# UV_LED.net
KiCad netlist of a schematic drawn in Altium Designer
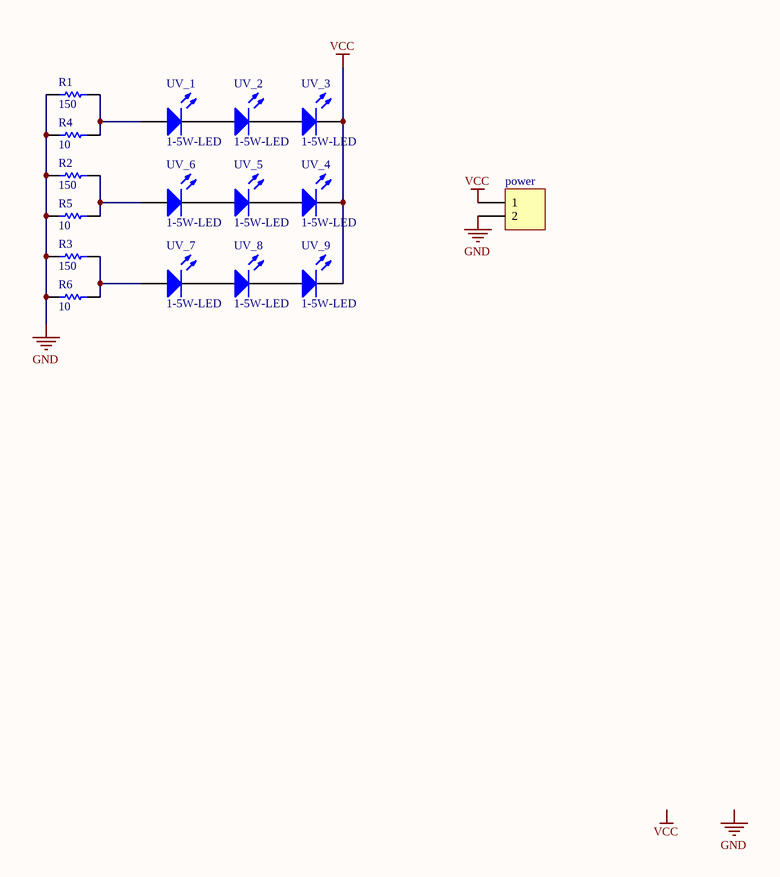
[diagram p0: UV LED.SchDoc]

(export (version "E")
  (design (tool "Eeschema 10.0.6"))
  (components
    (comp (ref "power")
      (value "Header 2")
      (footprint "HDR1X2")
      (description "Header, 2-Pin")
      (fields (field (name "PUBLISHER") "Altium Limited"))
      (libsource (lib "Miscellaneous Connectors") (part "Header 2"))
    )
    (comp (ref "R1")
      (value "150")
      (footprint "AXIAL-0.3")
      (description "Resistor")
      (fields (field (name "Comment") "Res1") (field (name "PUBLISHER") "Altium Limited"))
      (libsource (lib "Miscellaneous Devices") (part "Res1"))
    )
    (comp (ref "R2")
      (value "150")
      (footprint "AXIAL-0.3")
      (description "Resistor")
      (fields (field (name "Comment") "Res1") (field (name "PUBLISHER") "Altium Limited"))
      (libsource (lib "Miscellaneous Devices") (part "Res1"))
    )
    (comp (ref "R3")
      (value "150")
      (footprint "AXIAL-0.3")
      (description "Resistor")
      (fields (field (name "Comment") "Res1") (field (name "PUBLISHER") "Altium Limited"))
      (libsource (lib "Miscellaneous Devices") (part "Res1"))
    )
    (comp (ref "R4")
      (value "10")
      (footprint "AXIAL-0.3")
      (description "Resistor")
      (fields (field (name "Comment") "Res1") (field (name "PUBLISHER") "Altium Limited"))
      (libsource (lib "Miscellaneous Devices") (part "Res1"))
    )
    (comp (ref "R5")
      (value "10")
      (footprint "AXIAL-0.3")
      (description "Resistor")
      (fields (field (name "Comment") "Res1") (field (name "PUBLISHER") "Altium Limited"))
      (libsource (lib "Miscellaneous Devices") (part "Res1"))
    )
    (comp (ref "R6")
      (value "10")
      (footprint "AXIAL-0.3")
      (description "Resistor")
      (fields (field (name "Comment") "Res1") (field (name "PUBLISHER") "Altium Limited"))
      (libsource (lib "Miscellaneous Devices") (part "Res1"))
    )
    (comp (ref "UV_1")
      (value "1-5W-LED")
      (footprint "Highpwr_SMT_LED")
      (libsource (lib "arad") (part "1-5W-LED"))
    )
    (comp (ref "UV_2")
      (value "1-5W-LED")
      (footprint "Highpwr_SMT_LED")
      (libsource (lib "arad") (part "1-5W-LED"))
    )
    (comp (ref "UV_3")
      (value "1-5W-LED")
      (footprint "Highpwr_SMT_LED")
      (libsource (lib "arad") (part "1-5W-LED"))
    )
    (comp (ref "UV_4")
      (value "1-5W-LED")
      (footprint "Highpwr_SMT_LED")
      (libsource (lib "arad") (part "1-5W-LED"))
    )
    (comp (ref "UV_5")
      (value "1-5W-LED")
      (footprint "Highpwr_SMT_LED")
      (libsource (lib "arad") (part "1-5W-LED"))
    )
    (comp (ref "UV_6")
      (value "1-5W-LED")
      (footprint "Highpwr_SMT_LED")
      (libsource (lib "arad") (part "1-5W-LED"))
    )
    (comp (ref "UV_7")
      (value "1-5W-LED")
      (footprint "Highpwr_SMT_LED")
      (libsource (lib "arad") (part "1-5W-LED"))
    )
    (comp (ref "UV_8")
      (value "1-5W-LED")
      (footprint "Highpwr_SMT_LED")
      (libsource (lib "arad") (part "1-5W-LED"))
    )
    (comp (ref "UV_9")
      (value "1-5W-LED")
      (footprint "Highpwr_SMT_LED")
      (libsource (lib "arad") (part "1-5W-LED"))
    )
  )
  (nets
    (net (code "1") (name "GND") (class "Default")
      (node (ref "R1") (pin "1") (pinfunction "1_1") (pintype "passive"))
      (node (ref "R2") (pin "1") (pinfunction "1_1") (pintype "passive"))
      (node (ref "R3") (pin "1") (pinfunction "1_1") (pintype "passive"))
      (node (ref "R4") (pin "1") (pinfunction "1_1") (pintype "passive"))
      (node (ref "R5") (pin "1") (pinfunction "1_1") (pintype "passive"))
      (node (ref "R6") (pin "1") (pinfunction "1_1") (pintype "passive"))
      (node (ref "power") (pin "2") (pinfunction "2_2") (pintype "passive"))
    )
    (net (code "2") (name "Net-(UV_1-A)") (class "Default")
      (node (ref "R1") (pin "2") (pinfunction "2_2") (pintype "passive"))
      (node (ref "R4") (pin "2") (pinfunction "2_2") (pintype "passive"))
      (node (ref "UV_1") (pin "1") (pinfunction "A_1") (pintype "passive"))
    )
    (net (code "3") (name "Net-(UV_1-K)") (class "Default")
      (node (ref "UV_1") (pin "2") (pinfunction "K_2") (pintype "passive"))
      (node (ref "UV_2") (pin "1") (pinfunction "A_1") (pintype "passive"))
    )
    (net (code "4") (name "Net-(UV_2-K)") (class "Default")
      (node (ref "UV_2") (pin "2") (pinfunction "K_2") (pintype "passive"))
      (node (ref "UV_3") (pin "1") (pinfunction "A_1") (pintype "passive"))
    )
    (net (code "5") (name "Net-(UV_4-A)") (class "Default")
      (node (ref "UV_4") (pin "1") (pinfunction "A_1") (pintype "passive"))
      (node (ref "UV_5") (pin "2") (pinfunction "K_2") (pintype "passive"))
    )
    (net (code "6") (name "Net-(UV_5-A)") (class "Default")
      (node (ref "UV_5") (pin "1") (pinfunction "A_1") (pintype "passive"))
      (node (ref "UV_6") (pin "2") (pinfunction "K_2") (pintype "passive"))
    )
    (net (code "7") (name "Net-(UV_6-A)") (class "Default")
      (node (ref "R2") (pin "2") (pinfunction "2_2") (pintype "passive"))
      (node (ref "R5") (pin "2") (pinfunction "2_2") (pintype "passive"))
      (node (ref "UV_6") (pin "1") (pinfunction "A_1") (pintype "passive"))
    )
    (net (code "8") (name "Net-(UV_7-A)") (class "Default")
      (node (ref "R3") (pin "2") (pinfunction "2_2") (pintype "passive"))
      (node (ref "R6") (pin "2") (pinfunction "2_2") (pintype "passive"))
      (node (ref "UV_7") (pin "1") (pinfunction "A_1") (pintype "passive"))
    )
    (net (code "9") (name "Net-(UV_7-K)") (class "Default")
      (node (ref "UV_7") (pin "2") (pinfunction "K_2") (pintype "passive"))
      (node (ref "UV_8") (pin "1") (pinfunction "A_1") (pintype "passive"))
    )
    (net (code "10") (name "Net-(UV_8-K)") (class "Default")
      (node (ref "UV_8") (pin "2") (pinfunction "K_2") (pintype "passive"))
      (node (ref "UV_9") (pin "1") (pinfunction "A_1") (pintype "passive"))
    )
    (net (code "11") (name "VCC") (class "Default")
      (node (ref "UV_3") (pin "2") (pinfunction "K_2") (pintype "passive"))
      (node (ref "UV_4") (pin "2") (pinfunction "K_2") (pintype "passive"))
      (node (ref "UV_9") (pin "2") (pinfunction "K_2") (pintype "passive"))
      (node (ref "power") (pin "1") (pinfunction "1_1") (pintype "passive"))
    )
  )
)
